# QCW_MMC_PCBA.net
KiCad netlist of a schematic drawn in Altium Designer
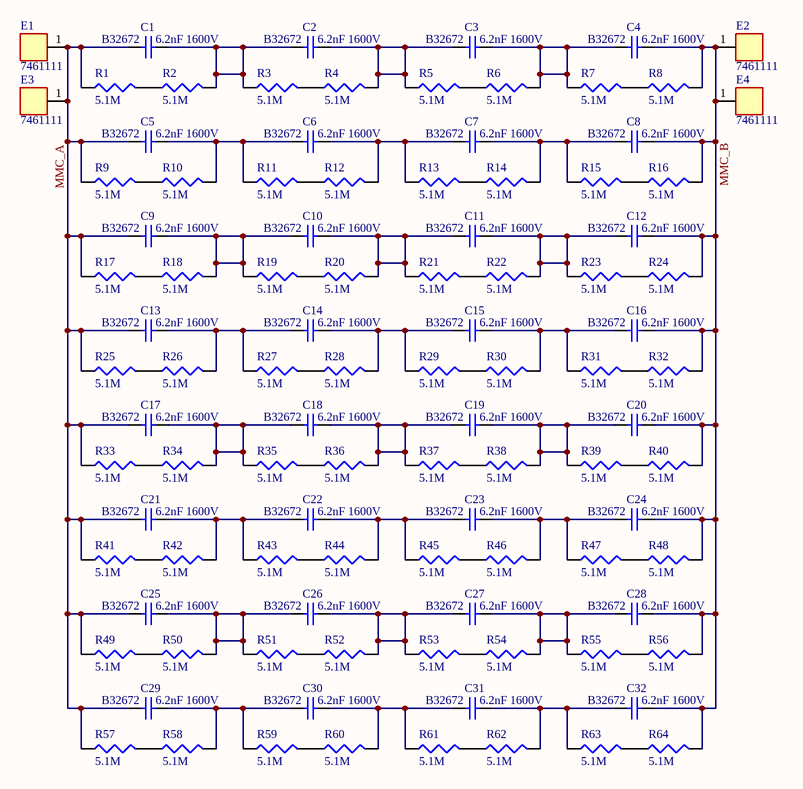
[diagram p0: QCW MMC PCBA.SchDoc]

(export (version "E")
  (design (tool "Eeschema 10.0.6"))
  (components
    (comp (ref "C1")
      (value "B32672")
      (footprint "B32672 6n2 1600V")
      (description "Capacitor")
      (fields (field (name "ALTIUM_VALUE") "6.2nF 1600V") (field (name "PUBLISHER") "Altium Limited"))
      (libsource (lib "Miscellaneous Devices") (part "Cap"))
    )
    (comp (ref "C2")
      (value "B32672")
      (footprint "B32672 6n2 1600V")
      (description "Capacitor")
      (fields (field (name "ALTIUM_VALUE") "6.2nF 1600V") (field (name "PUBLISHER") "Altium Limited"))
      (libsource (lib "Miscellaneous Devices") (part "Cap"))
    )
    (comp (ref "C3")
      (value "B32672")
      (footprint "B32672 6n2 1600V")
      (description "Capacitor")
      (fields (field (name "ALTIUM_VALUE") "6.2nF 1600V") (field (name "PUBLISHER") "Altium Limited"))
      (libsource (lib "Miscellaneous Devices") (part "Cap"))
    )
    (comp (ref "C4")
      (value "B32672")
      (footprint "B32672 6n2 1600V")
      (description "Capacitor")
      (fields (field (name "ALTIUM_VALUE") "6.2nF 1600V") (field (name "PUBLISHER") "Altium Limited"))
      (libsource (lib "Miscellaneous Devices") (part "Cap"))
    )
    (comp (ref "C5")
      (value "B32672")
      (footprint "B32672 6n2 1600V")
      (description "Capacitor")
      (fields (field (name "ALTIUM_VALUE") "6.2nF 1600V") (field (name "PUBLISHER") "Altium Limited"))
      (libsource (lib "Miscellaneous Devices") (part "Cap"))
    )
    (comp (ref "C6")
      (value "B32672")
      (footprint "B32672 6n2 1600V")
      (description "Capacitor")
      (fields (field (name "ALTIUM_VALUE") "6.2nF 1600V") (field (name "PUBLISHER") "Altium Limited"))
      (libsource (lib "Miscellaneous Devices") (part "Cap"))
    )
    (comp (ref "C7")
      (value "B32672")
      (footprint "B32672 6n2 1600V")
      (description "Capacitor")
      (fields (field (name "ALTIUM_VALUE") "6.2nF 1600V") (field (name "PUBLISHER") "Altium Limited"))
      (libsource (lib "Miscellaneous Devices") (part "Cap"))
    )
    (comp (ref "C8")
      (value "B32672")
      (footprint "B32672 6n2 1600V")
      (description "Capacitor")
      (fields (field (name "ALTIUM_VALUE") "6.2nF 1600V") (field (name "PUBLISHER") "Altium Limited"))
      (libsource (lib "Miscellaneous Devices") (part "Cap"))
    )
    (comp (ref "C9")
      (value "B32672")
      (footprint "B32672 6n2 1600V")
      (description "Capacitor")
      (fields (field (name "ALTIUM_VALUE") "6.2nF 1600V") (field (name "PUBLISHER") "Altium Limited"))
      (libsource (lib "Miscellaneous Devices") (part "Cap"))
    )
    (comp (ref "C10")
      (value "B32672")
      (footprint "B32672 6n2 1600V")
      (description "Capacitor")
      (fields (field (name "ALTIUM_VALUE") "6.2nF 1600V") (field (name "PUBLISHER") "Altium Limited"))
      (libsource (lib "Miscellaneous Devices") (part "Cap"))
    )
    (comp (ref "C11")
      (value "B32672")
      (footprint "B32672 6n2 1600V")
      (description "Capacitor")
      (fields (field (name "ALTIUM_VALUE") "6.2nF 1600V") (field (name "PUBLISHER") "Altium Limited"))
      (libsource (lib "Miscellaneous Devices") (part "Cap"))
    )
    (comp (ref "C12")
      (value "B32672")
      (footprint "B32672 6n2 1600V")
      (description "Capacitor")
      (fields (field (name "ALTIUM_VALUE") "6.2nF 1600V") (field (name "PUBLISHER") "Altium Limited"))
      (libsource (lib "Miscellaneous Devices") (part "Cap"))
    )
    (comp (ref "C13")
      (value "B32672")
      (footprint "B32672 6n2 1600V")
      (description "Capacitor")
      (fields (field (name "ALTIUM_VALUE") "6.2nF 1600V") (field (name "PUBLISHER") "Altium Limited"))
      (libsource (lib "Miscellaneous Devices") (part "Cap"))
    )
    (comp (ref "C14")
      (value "B32672")
      (footprint "B32672 6n2 1600V")
      (description "Capacitor")
      (fields (field (name "ALTIUM_VALUE") "6.2nF 1600V") (field (name "PUBLISHER") "Altium Limited"))
      (libsource (lib "Miscellaneous Devices") (part "Cap"))
    )
    (comp (ref "C15")
      (value "B32672")
      (footprint "B32672 6n2 1600V")
      (description "Capacitor")
      (fields (field (name "ALTIUM_VALUE") "6.2nF 1600V") (field (name "PUBLISHER") "Altium Limited"))
      (libsource (lib "Miscellaneous Devices") (part "Cap"))
    )
    (comp (ref "C16")
      (value "B32672")
      (footprint "B32672 6n2 1600V")
      (description "Capacitor")
      (fields (field (name "ALTIUM_VALUE") "6.2nF 1600V") (field (name "PUBLISHER") "Altium Limited"))
      (libsource (lib "Miscellaneous Devices") (part "Cap"))
    )
    (comp (ref "C17")
      (value "B32672")
      (footprint "B32672 6n2 1600V")
      (description "Capacitor")
      (fields (field (name "ALTIUM_VALUE") "6.2nF 1600V") (field (name "PUBLISHER") "Altium Limited"))
      (libsource (lib "Miscellaneous Devices") (part "Cap"))
    )
    (comp (ref "C18")
      (value "B32672")
      (footprint "B32672 6n2 1600V")
      (description "Capacitor")
      (fields (field (name "ALTIUM_VALUE") "6.2nF 1600V") (field (name "PUBLISHER") "Altium Limited"))
      (libsource (lib "Miscellaneous Devices") (part "Cap"))
    )
    (comp (ref "C19")
      (value "B32672")
      (footprint "B32672 6n2 1600V")
      (description "Capacitor")
      (fields (field (name "ALTIUM_VALUE") "6.2nF 1600V") (field (name "PUBLISHER") "Altium Limited"))
      (libsource (lib "Miscellaneous Devices") (part "Cap"))
    )
    (comp (ref "C20")
      (value "B32672")
      (footprint "B32672 6n2 1600V")
      (description "Capacitor")
      (fields (field (name "ALTIUM_VALUE") "6.2nF 1600V") (field (name "PUBLISHER") "Altium Limited"))
      (libsource (lib "Miscellaneous Devices") (part "Cap"))
    )
    (comp (ref "C21")
      (value "B32672")
      (footprint "B32672 6n2 1600V")
      (description "Capacitor")
      (fields (field (name "ALTIUM_VALUE") "6.2nF 1600V") (field (name "PUBLISHER") "Altium Limited"))
      (libsource (lib "Miscellaneous Devices") (part "Cap"))
    )
    (comp (ref "C22")
      (value "B32672")
      (footprint "B32672 6n2 1600V")
      (description "Capacitor")
      (fields (field (name "ALTIUM_VALUE") "6.2nF 1600V") (field (name "PUBLISHER") "Altium Limited"))
      (libsource (lib "Miscellaneous Devices") (part "Cap"))
    )
    (comp (ref "C23")
      (value "B32672")
      (footprint "B32672 6n2 1600V")
      (description "Capacitor")
      (fields (field (name "ALTIUM_VALUE") "6.2nF 1600V") (field (name "PUBLISHER") "Altium Limited"))
      (libsource (lib "Miscellaneous Devices") (part "Cap"))
    )
    (comp (ref "C24")
      (value "B32672")
      (footprint "B32672 6n2 1600V")
      (description "Capacitor")
      (fields (field (name "ALTIUM_VALUE") "6.2nF 1600V") (field (name "PUBLISHER") "Altium Limited"))
      (libsource (lib "Miscellaneous Devices") (part "Cap"))
    )
    (comp (ref "C25")
      (value "B32672")
      (footprint "B32672 6n2 1600V")
      (description "Capacitor")
      (fields (field (name "ALTIUM_VALUE") "6.2nF 1600V") (field (name "PUBLISHER") "Altium Limited"))
      (libsource (lib "Miscellaneous Devices") (part "Cap"))
    )
    (comp (ref "C26")
      (value "B32672")
      (footprint "B32672 6n2 1600V")
      (description "Capacitor")
      (fields (field (name "ALTIUM_VALUE") "6.2nF 1600V") (field (name "PUBLISHER") "Altium Limited"))
      (libsource (lib "Miscellaneous Devices") (part "Cap"))
    )
    (comp (ref "C27")
      (value "B32672")
      (footprint "B32672 6n2 1600V")
      (description "Capacitor")
      (fields (field (name "ALTIUM_VALUE") "6.2nF 1600V") (field (name "PUBLISHER") "Altium Limited"))
      (libsource (lib "Miscellaneous Devices") (part "Cap"))
    )
    (comp (ref "C28")
      (value "B32672")
      (footprint "B32672 6n2 1600V")
      (description "Capacitor")
      (fields (field (name "ALTIUM_VALUE") "6.2nF 1600V") (field (name "PUBLISHER") "Altium Limited"))
      (libsource (lib "Miscellaneous Devices") (part "Cap"))
    )
    (comp (ref "C29")
      (value "B32672")
      (footprint "B32672 6n2 1600V")
      (description "Capacitor")
      (fields (field (name "ALTIUM_VALUE") "6.2nF 1600V") (field (name "PUBLISHER") "Altium Limited"))
      (libsource (lib "Miscellaneous Devices") (part "Cap"))
    )
    (comp (ref "C30")
      (value "B32672")
      (footprint "B32672 6n2 1600V")
      (description "Capacitor")
      (fields (field (name "ALTIUM_VALUE") "6.2nF 1600V") (field (name "PUBLISHER") "Altium Limited"))
      (libsource (lib "Miscellaneous Devices") (part "Cap"))
    )
    (comp (ref "C31")
      (value "B32672")
      (footprint "B32672 6n2 1600V")
      (description "Capacitor")
      (fields (field (name "ALTIUM_VALUE") "6.2nF 1600V") (field (name "PUBLISHER") "Altium Limited"))
      (libsource (lib "Miscellaneous Devices") (part "Cap"))
    )
    (comp (ref "C32")
      (value "B32672")
      (footprint "B32672 6n2 1600V")
      (description "Capacitor")
      (fields (field (name "ALTIUM_VALUE") "6.2nF 1600V") (field (name "PUBLISHER") "Altium Limited"))
      (libsource (lib "Miscellaneous Devices") (part "Cap"))
    )
    (comp (ref "E1")
      (value "7461111")
      (footprint "7461111_HAL Surface")
      (description "WP-RAFU 90° with Full Plain Pin Plate, M4, thr 5mm")
      (fields (field (name "MANUFACTURER") "Wurth Elektronik") (field (name "CREATED BY") "Baojun Chen"))
      (libsource (lib "TV_Altium_library") (part "WP-RAFU,  7461111"))
    )
    (comp (ref "E2")
      (value "7461111")
      (footprint "7461111_HAL Surface")
      (description "WP-RAFU 90° with Full Plain Pin Plate, M4, thr 5mm")
      (fields (field (name "MANUFACTURER") "Wurth Elektronik") (field (name "CREATED BY") "Baojun Chen"))
      (libsource (lib "") (part "WP-RAFU,  7461111_1"))
    )
    (comp (ref "E3")
      (value "7461111")
      (footprint "7461111_HAL Surface")
      (description "WP-RAFU 90° with Full Plain Pin Plate, M4, thr 5mm")
      (fields (field (name "MANUFACTURER") "Wurth Elektronik") (field (name "CREATED BY") "Baojun Chen"))
      (libsource (lib "TV_Altium_library") (part "WP-RAFU,  7461111"))
    )
    (comp (ref "E4")
      (value "7461111")
      (footprint "7461111_HAL Surface")
      (description "WP-RAFU 90° with Full Plain Pin Plate, M4, thr 5mm")
      (fields (field (name "MANUFACTURER") "Wurth Elektronik") (field (name "CREATED BY") "Baojun Chen"))
      (libsource (lib "") (part "WP-RAFU,  7461111_1"))
    )
    (comp (ref "R1")
      (value "5.1M")
      (description "Resistor")
      (fields (field (name "Comment") "HV 1206 Resistor") (field (name "PUBLISHER") "Altium Limited"))
      (libsource (lib "Miscellaneous Devices") (part "Res3"))
    )
    (comp (ref "R2")
      (value "5.1M")
      (description "Resistor")
      (fields (field (name "Comment") "HV 1206 Resistor") (field (name "PUBLISHER") "Altium Limited"))
      (libsource (lib "Miscellaneous Devices") (part "Res3"))
    )
    (comp (ref "R3")
      (value "5.1M")
      (description "Resistor")
      (fields (field (name "Comment") "HV 1206 Resistor") (field (name "PUBLISHER") "Altium Limited"))
      (libsource (lib "Miscellaneous Devices") (part "Res3"))
    )
    (comp (ref "R4")
      (value "5.1M")
      (description "Resistor")
      (fields (field (name "Comment") "HV 1206 Resistor") (field (name "PUBLISHER") "Altium Limited"))
      (libsource (lib "Miscellaneous Devices") (part "Res3"))
    )
    (comp (ref "R5")
      (value "5.1M")
      (description "Resistor")
      (fields (field (name "Comment") "HV 1206 Resistor") (field (name "PUBLISHER") "Altium Limited"))
      (libsource (lib "Miscellaneous Devices") (part "Res3"))
    )
    (comp (ref "R6")
      (value "5.1M")
      (description "Resistor")
      (fields (field (name "Comment") "HV 1206 Resistor") (field (name "PUBLISHER") "Altium Limited"))
      (libsource (lib "Miscellaneous Devices") (part "Res3"))
    )
    (comp (ref "R7")
      (value "5.1M")
      (description "Resistor")
      (fields (field (name "Comment") "HV 1206 Resistor") (field (name "PUBLISHER") "Altium Limited"))
      (libsource (lib "Miscellaneous Devices") (part "Res3"))
    )
    (comp (ref "R8")
      (value "5.1M")
      (description "Resistor")
      (fields (field (name "Comment") "HV 1206 Resistor") (field (name "PUBLISHER") "Altium Limited"))
      (libsource (lib "Miscellaneous Devices") (part "Res3"))
    )
    (comp (ref "R9")
      (value "5.1M")
      (description "Resistor")
      (fields (field (name "Comment") "HV 1206 Resistor") (field (name "PUBLISHER") "Altium Limited"))
      (libsource (lib "Miscellaneous Devices") (part "Res3"))
    )
    (comp (ref "R10")
      (value "5.1M")
      (description "Resistor")
      (fields (field (name "Comment") "HV 1206 Resistor") (field (name "PUBLISHER") "Altium Limited"))
      (libsource (lib "Miscellaneous Devices") (part "Res3"))
    )
    (comp (ref "R11")
      (value "5.1M")
      (description "Resistor")
      (fields (field (name "Comment") "HV 1206 Resistor") (field (name "PUBLISHER") "Altium Limited"))
      (libsource (lib "Miscellaneous Devices") (part "Res3"))
    )
    (comp (ref "R12")
      (value "5.1M")
      (description "Resistor")
      (fields (field (name "Comment") "HV 1206 Resistor") (field (name "PUBLISHER") "Altium Limited"))
      (libsource (lib "Miscellaneous Devices") (part "Res3"))
    )
    (comp (ref "R13")
      (value "5.1M")
      (description "Resistor")
      (fields (field (name "Comment") "HV 1206 Resistor") (field (name "PUBLISHER") "Altium Limited"))
      (libsource (lib "Miscellaneous Devices") (part "Res3"))
    )
    (comp (ref "R14")
      (value "5.1M")
      (description "Resistor")
      (fields (field (name "Comment") "HV 1206 Resistor") (field (name "PUBLISHER") "Altium Limited"))
      (libsource (lib "Miscellaneous Devices") (part "Res3"))
    )
    (comp (ref "R15")
      (value "5.1M")
      (description "Resistor")
      (fields (field (name "Comment") "HV 1206 Resistor") (field (name "PUBLISHER") "Altium Limited"))
      (libsource (lib "Miscellaneous Devices") (part "Res3"))
    )
    (comp (ref "R16")
      (value "5.1M")
      (description "Resistor")
      (fields (field (name "Comment") "HV 1206 Resistor") (field (name "PUBLISHER") "Altium Limited"))
      (libsource (lib "Miscellaneous Devices") (part "Res3"))
    )
    (comp (ref "R17")
      (value "5.1M")
      (description "Resistor")
      (fields (field (name "Comment") "HV 1206 Resistor") (field (name "PUBLISHER") "Altium Limited"))
      (libsource (lib "Miscellaneous Devices") (part "Res3"))
    )
    (comp (ref "R18")
      (value "5.1M")
      (description "Resistor")
      (fields (field (name "Comment") "HV 1206 Resistor") (field (name "PUBLISHER") "Altium Limited"))
      (libsource (lib "Miscellaneous Devices") (part "Res3"))
    )
    (comp (ref "R19")
      (value "5.1M")
      (description "Resistor")
      (fields (field (name "Comment") "HV 1206 Resistor") (field (name "PUBLISHER") "Altium Limited"))
      (libsource (lib "Miscellaneous Devices") (part "Res3"))
    )
    (comp (ref "R20")
      (value "5.1M")
      (description "Resistor")
      (fields (field (name "Comment") "HV 1206 Resistor") (field (name "PUBLISHER") "Altium Limited"))
      (libsource (lib "Miscellaneous Devices") (part "Res3"))
    )
    (comp (ref "R21")
      (value "5.1M")
      (description "Resistor")
      (fields (field (name "Comment") "HV 1206 Resistor") (field (name "PUBLISHER") "Altium Limited"))
      (libsource (lib "Miscellaneous Devices") (part "Res3"))
    )
    (comp (ref "R22")
      (value "5.1M")
      (description "Resistor")
      (fields (field (name "Comment") "HV 1206 Resistor") (field (name "PUBLISHER") "Altium Limited"))
      (libsource (lib "Miscellaneous Devices") (part "Res3"))
    )
    (comp (ref "R23")
      (value "5.1M")
      (description "Resistor")
      (fields (field (name "Comment") "HV 1206 Resistor") (field (name "PUBLISHER") "Altium Limited"))
      (libsource (lib "Miscellaneous Devices") (part "Res3"))
    )
    (comp (ref "R24")
      (value "5.1M")
      (description "Resistor")
      (fields (field (name "Comment") "HV 1206 Resistor") (field (name "PUBLISHER") "Altium Limited"))
      (libsource (lib "Miscellaneous Devices") (part "Res3"))
    )
    (comp (ref "R25")
      (value "5.1M")
      (description "Resistor")
      (fields (field (name "Comment") "HV 1206 Resistor") (field (name "PUBLISHER") "Altium Limited"))
      (libsource (lib "Miscellaneous Devices") (part "Res3"))
    )
    (comp (ref "R26")
      (value "5.1M")
      (description "Resistor")
      (fields (field (name "Comment") "HV 1206 Resistor") (field (name "PUBLISHER") "Altium Limited"))
      (libsource (lib "Miscellaneous Devices") (part "Res3"))
    )
    (comp (ref "R27")
      (value "5.1M")
      (description "Resistor")
      (fields (field (name "Comment") "HV 1206 Resistor") (field (name "PUBLISHER") "Altium Limited"))
      (libsource (lib "Miscellaneous Devices") (part "Res3"))
    )
    (comp (ref "R28")
      (value "5.1M")
      (description "Resistor")
      (fields (field (name "Comment") "HV 1206 Resistor") (field (name "PUBLISHER") "Altium Limited"))
      (libsource (lib "Miscellaneous Devices") (part "Res3"))
    )
    (comp (ref "R29")
      (value "5.1M")
      (description "Resistor")
      (fields (field (name "Comment") "HV 1206 Resistor") (field (name "PUBLISHER") "Altium Limited"))
      (libsource (lib "Miscellaneous Devices") (part "Res3"))
    )
    (comp (ref "R30")
      (value "5.1M")
      (description "Resistor")
      (fields (field (name "Comment") "HV 1206 Resistor") (field (name "PUBLISHER") "Altium Limited"))
      (libsource (lib "Miscellaneous Devices") (part "Res3"))
    )
    (comp (ref "R31")
      (value "5.1M")
      (description "Resistor")
      (fields (field (name "Comment") "HV 1206 Resistor") (field (name "PUBLISHER") "Altium Limited"))
      (libsource (lib "Miscellaneous Devices") (part "Res3"))
    )
    (comp (ref "R32")
      (value "5.1M")
      (description "Resistor")
      (fields (field (name "Comment") "HV 1206 Resistor") (field (name "PUBLISHER") "Altium Limited"))
      (libsource (lib "Miscellaneous Devices") (part "Res3"))
    )
    (comp (ref "R33")
      (value "5.1M")
      (description "Resistor")
      (fields (field (name "Comment") "HV 1206 Resistor") (field (name "PUBLISHER") "Altium Limited"))
      (libsource (lib "Miscellaneous Devices") (part "Res3"))
    )
    (comp (ref "R34")
      (value "5.1M")
      (description "Resistor")
      (fields (field (name "Comment") "HV 1206 Resistor") (field (name "PUBLISHER") "Altium Limited"))
      (libsource (lib "Miscellaneous Devices") (part "Res3"))
    )
    (comp (ref "R35")
      (value "5.1M")
      (description "Resistor")
      (fields (field (name "Comment") "HV 1206 Resistor") (field (name "PUBLISHER") "Altium Limited"))
      (libsource (lib "Miscellaneous Devices") (part "Res3"))
    )
    (comp (ref "R36")
      (value "5.1M")
      (description "Resistor")
      (fields (field (name "Comment") "HV 1206 Resistor") (field (name "PUBLISHER") "Altium Limited"))
      (libsource (lib "Miscellaneous Devices") (part "Res3"))
    )
    (comp (ref "R37")
      (value "5.1M")
      (description "Resistor")
      (fields (field (name "Comment") "HV 1206 Resistor") (field (name "PUBLISHER") "Altium Limited"))
      (libsource (lib "Miscellaneous Devices") (part "Res3"))
    )
    (comp (ref "R38")
      (value "5.1M")
      (description "Resistor")
      (fields (field (name "Comment") "HV 1206 Resistor") (field (name "PUBLISHER") "Altium Limited"))
      (libsource (lib "Miscellaneous Devices") (part "Res3"))
    )
    (comp (ref "R39")
      (value "5.1M")
      (description "Resistor")
      (fields (field (name "Comment") "HV 1206 Resistor") (field (name "PUBLISHER") "Altium Limited"))
      (libsource (lib "Miscellaneous Devices") (part "Res3"))
    )
    (comp (ref "R40")
      (value "5.1M")
      (description "Resistor")
      (fields (field (name "Comment") "HV 1206 Resistor") (field (name "PUBLISHER") "Altium Limited"))
      (libsource (lib "Miscellaneous Devices") (part "Res3"))
    )
    (comp (ref "R41")
      (value "5.1M")
      (description "Resistor")
      (fields (field (name "Comment") "HV 1206 Resistor") (field (name "PUBLISHER") "Altium Limited"))
      (libsource (lib "Miscellaneous Devices") (part "Res3"))
    )
    (comp (ref "R42")
      (value "5.1M")
      (description "Resistor")
      (fields (field (name "Comment") "HV 1206 Resistor") (field (name "PUBLISHER") "Altium Limited"))
      (libsource (lib "Miscellaneous Devices") (part "Res3"))
    )
    (comp (ref "R43")
      (value "5.1M")
      (description "Resistor")
      (fields (field (name "Comment") "HV 1206 Resistor") (field (name "PUBLISHER") "Altium Limited"))
      (libsource (lib "Miscellaneous Devices") (part "Res3"))
    )
    (comp (ref "R44")
      (value "5.1M")
      (description "Resistor")
      (fields (field (name "Comment") "HV 1206 Resistor") (field (name "PUBLISHER") "Altium Limited"))
      (libsource (lib "Miscellaneous Devices") (part "Res3"))
    )
    (comp (ref "R45")
      (value "5.1M")
      (description "Resistor")
      (fields (field (name "Comment") "HV 1206 Resistor") (field (name "PUBLISHER") "Altium Limited"))
      (libsource (lib "Miscellaneous Devices") (part "Res3"))
    )
    (comp (ref "R46")
      (value "5.1M")
      (description "Resistor")
      (fields (field (name "Comment") "HV 1206 Resistor") (field (name "PUBLISHER") "Altium Limited"))
      (libsource (lib "Miscellaneous Devices") (part "Res3"))
    )
    (comp (ref "R47")
      (value "5.1M")
      (description "Resistor")
      (fields (field (name "Comment") "HV 1206 Resistor") (field (name "PUBLISHER") "Altium Limited"))
      (libsource (lib "Miscellaneous Devices") (part "Res3"))
    )
    (comp (ref "R48")
      (value "5.1M")
      (description "Resistor")
      (fields (field (name "Comment") "HV 1206 Resistor") (field (name "PUBLISHER") "Altium Limited"))
      (libsource (lib "Miscellaneous Devices") (part "Res3"))
    )
    (comp (ref "R49")
      (value "5.1M")
      (description "Resistor")
      (fields (field (name "Comment") "HV 1206 Resistor") (field (name "PUBLISHER") "Altium Limited"))
      (libsource (lib "Miscellaneous Devices") (part "Res3"))
    )
    (comp (ref "R50")
      (value "5.1M")
      (description "Resistor")
      (fields (field (name "Comment") "HV 1206 Resistor") (field (name "PUBLISHER") "Altium Limited"))
      (libsource (lib "Miscellaneous Devices") (part "Res3"))
    )
    (comp (ref "R51")
      (value "5.1M")
      (description "Resistor")
      (fields (field (name "Comment") "HV 1206 Resistor") (field (name "PUBLISHER") "Altium Limited"))
      (libsource (lib "Miscellaneous Devices") (part "Res3"))
    )
    (comp (ref "R52")
      (value "5.1M")
      (description "Resistor")
      (fields (field (name "Comment") "HV 1206 Resistor") (field (name "PUBLISHER") "Altium Limited"))
      (libsource (lib "Miscellaneous Devices") (part "Res3"))
    )
    (comp (ref "R53")
      (value "5.1M")
      (description "Resistor")
      (fields (field (name "Comment") "HV 1206 Resistor") (field (name "PUBLISHER") "Altium Limited"))
      (libsource (lib "Miscellaneous Devices") (part "Res3"))
    )
    (comp (ref "R54")
      (value "5.1M")
      (description "Resistor")
      (fields (field (name "Comment") "HV 1206 Resistor") (field (name "PUBLISHER") "Altium Limited"))
      (libsource (lib "Miscellaneous Devices") (part "Res3"))
    )
    (comp (ref "R55")
      (value "5.1M")
      (description "Resistor")
      (fields (field (name "Comment") "HV 1206 Resistor") (field (name "PUBLISHER") "Altium Limited"))
      (libsource (lib "Miscellaneous Devices") (part "Res3"))
    )
    (comp (ref "R56")
      (value "5.1M")
      (description "Resistor")
      (fields (field (name "Comment") "HV 1206 Resistor") (field (name "PUBLISHER") "Altium Limited"))
      (libsource (lib "Miscellaneous Devices") (part "Res3"))
    )
    (comp (ref "R57")
      (value "5.1M")
      (description "Resistor")
      (fields (field (name "Comment") "HV 1206 Resistor") (field (name "PUBLISHER") "Altium Limited"))
      (libsource (lib "Miscellaneous Devices") (part "Res3"))
    )
    (comp (ref "R58")
      (value "5.1M")
      (description "Resistor")
      (fields (field (name "Comment") "HV 1206 Resistor") (field (name "PUBLISHER") "Altium Limited"))
      (libsource (lib "Miscellaneous Devices") (part "Res3"))
    )
    (comp (ref "R59")
      (value "5.1M")
      (description "Resistor")
      (fields (field (name "Comment") "HV 1206 Resistor") (field (name "PUBLISHER") "Altium Limited"))
      (libsource (lib "Miscellaneous Devices") (part "Res3"))
    )
    (comp (ref "R60")
      (value "5.1M")
      (description "Resistor")
      (fields (field (name "Comment") "HV 1206 Resistor") (field (name "PUBLISHER") "Altium Limited"))
      (libsource (lib "Miscellaneous Devices") (part "Res3"))
    )
    (comp (ref "R61")
      (value "5.1M")
      (description "Resistor")
      (fields (field (name "Comment") "HV 1206 Resistor") (field (name "PUBLISHER") "Altium Limited"))
      (libsource (lib "Miscellaneous Devices") (part "Res3"))
    )
    (comp (ref "R62")
      (value "5.1M")
      (description "Resistor")
      (fields (field (name "Comment") "HV 1206 Resistor") (field (name "PUBLISHER") "Altium Limited"))
      (libsource (lib "Miscellaneous Devices") (part "Res3"))
    )
    (comp (ref "R63")
      (value "5.1M")
      (description "Resistor")
      (fields (field (name "Comment") "HV 1206 Resistor") (field (name "PUBLISHER") "Altium Limited"))
      (libsource (lib "Miscellaneous Devices") (part "Res3"))
    )
    (comp (ref "R64")
      (value "5.1M")
      (description "Resistor")
      (fields (field (name "Comment") "HV 1206 Resistor") (field (name "PUBLISHER") "Altium Limited"))
      (libsource (lib "Miscellaneous Devices") (part "Res3"))
    )
  )
  (nets
    (net (code "1") (name "/MMC_A") (class "Default")
      (node (ref "C1") (pin "1") (pinfunction "1_1") (pintype "passive"))
      (node (ref "C13") (pin "1") (pinfunction "1_1") (pintype "passive"))
      (node (ref "C17") (pin "1") (pinfunction "1_1") (pintype "passive"))
      (node (ref "C21") (pin "1") (pinfunction "1_1") (pintype "passive"))
      (node (ref "C25") (pin "1") (pinfunction "1_1") (pintype "passive"))
      (node (ref "C29") (pin "1") (pinfunction "1_1") (pintype "passive"))
      (node (ref "C5") (pin "1") (pinfunction "1_1") (pintype "passive"))
      (node (ref "C9") (pin "1") (pinfunction "1_1") (pintype "passive"))
      (node (ref "E1") (pin "1") (pinfunction "1_1") (pintype "passive"))
      (node (ref "E3") (pin "1") (pinfunction "1_1") (pintype "passive"))
      (node (ref "R1") (pin "1") (pinfunction "1_1") (pintype "passive"))
      (node (ref "R17") (pin "1") (pinfunction "1_1") (pintype "passive"))
      (node (ref "R25") (pin "1") (pinfunction "1_1") (pintype "passive"))
      (node (ref "R33") (pin "1") (pinfunction "1_1") (pintype "passive"))
      (node (ref "R41") (pin "1") (pinfunction "1_1") (pintype "passive"))
      (node (ref "R49") (pin "1") (pinfunction "1_1") (pintype "passive"))
      (node (ref "R57") (pin "1") (pinfunction "1_1") (pintype "passive"))
      (node (ref "R9") (pin "1") (pinfunction "1_1") (pintype "passive"))
    )
    (net (code "2") (name "/MMC_B") (class "Default")
      (node (ref "C12") (pin "2") (pinfunction "2_2") (pintype "passive"))
      (node (ref "C16") (pin "2") (pinfunction "2_2") (pintype "passive"))
      (node (ref "C20") (pin "2") (pinfunction "2_2") (pintype "passive"))
      (node (ref "C24") (pin "2") (pinfunction "2_2") (pintype "passive"))
      (node (ref "C28") (pin "2") (pinfunction "2_2") (pintype "passive"))
      (node (ref "C32") (pin "2") (pinfunction "2_2") (pintype "passive"))
      (node (ref "C4") (pin "2") (pinfunction "2_2") (pintype "passive"))
      (node (ref "C8") (pin "2") (pinfunction "2_2") (pintype "passive"))
      (node (ref "E2") (pin "1") (pinfunction "1_1") (pintype "passive"))
      (node (ref "E4") (pin "1") (pinfunction "1_1") (pintype "passive"))
      (node (ref "R16") (pin "2") (pinfunction "2_2") (pintype "passive"))
      (node (ref "R24") (pin "2") (pinfunction "2_2") (pintype "passive"))
      (node (ref "R32") (pin "2") (pinfunction "2_2") (pintype "passive"))
      (node (ref "R40") (pin "2") (pinfunction "2_2") (pintype "passive"))
      (node (ref "R48") (pin "2") (pinfunction "2_2") (pintype "passive"))
      (node (ref "R56") (pin "2") (pinfunction "2_2") (pintype "passive"))
      (node (ref "R64") (pin "2") (pinfunction "2_2") (pintype "passive"))
      (node (ref "R8") (pin "2") (pinfunction "2_2") (pintype "passive"))
    )
    (net (code "3") (name "Net-(C1-Pad2)") (class "Default")
      (node (ref "C1") (pin "2") (pinfunction "2_2") (pintype "passive"))
      (node (ref "C2") (pin "1") (pinfunction "1_1") (pintype "passive"))
      (node (ref "R2") (pin "2") (pinfunction "2_2") (pintype "passive"))
      (node (ref "R3") (pin "1") (pinfunction "1_1") (pintype "passive"))
    )
    (net (code "4") (name "Net-(C2-Pad2)") (class "Default")
      (node (ref "C2") (pin "2") (pinfunction "2_2") (pintype "passive"))
      (node (ref "C3") (pin "1") (pinfunction "1_1") (pintype "passive"))
      (node (ref "R4") (pin "2") (pinfunction "2_2") (pintype "passive"))
      (node (ref "R5") (pin "1") (pinfunction "1_1") (pintype "passive"))
    )
    (net (code "5") (name "Net-(C3-Pad2)") (class "Default")
      (node (ref "C3") (pin "2") (pinfunction "2_2") (pintype "passive"))
      (node (ref "C4") (pin "1") (pinfunction "1_1") (pintype "passive"))
      (node (ref "R6") (pin "2") (pinfunction "2_2") (pintype "passive"))
      (node (ref "R7") (pin "1") (pinfunction "1_1") (pintype "passive"))
    )
    (net (code "6") (name "Net-(C5-Pad2)") (class "Default")
      (node (ref "C5") (pin "2") (pinfunction "2_2") (pintype "passive"))
      (node (ref "C6") (pin "1") (pinfunction "1_1") (pintype "passive"))
      (node (ref "R10") (pin "2") (pinfunction "2_2") (pintype "passive"))
      (node (ref "R11") (pin "1") (pinfunction "1_1") (pintype "passive"))
    )
    (net (code "7") (name "Net-(C6-Pad2)") (class "Default")
      (node (ref "C6") (pin "2") (pinfunction "2_2") (pintype "passive"))
      (node (ref "C7") (pin "1") (pinfunction "1_1") (pintype "passive"))
      (node (ref "R12") (pin "2") (pinfunction "2_2") (pintype "passive"))
      (node (ref "R13") (pin "1") (pinfunction "1_1") (pintype "passive"))
    )
    (net (code "8") (name "Net-(C7-Pad2)") (class "Default")
      (node (ref "C7") (pin "2") (pinfunction "2_2") (pintype "passive"))
      (node (ref "C8") (pin "1") (pinfunction "1_1") (pintype "passive"))
      (node (ref "R14") (pin "2") (pinfunction "2_2") (pintype "passive"))
      (node (ref "R15") (pin "1") (pinfunction "1_1") (pintype "passive"))
    )
    (net (code "9") (name "Net-(C10-Pad1)") (class "Default")
      (node (ref "C10") (pin "1") (pinfunction "1_1") (pintype "passive"))
      (node (ref "C9") (pin "2") (pinfunction "2_2") (pintype "passive"))
      (node (ref "R18") (pin "2") (pinfunction "2_2") (pintype "passive"))
      (node (ref "R19") (pin "1") (pinfunction "1_1") (pintype "passive"))
    )
    (net (code "10") (name "Net-(C10-Pad2)") (class "Default")
      (node (ref "C10") (pin "2") (pinfunction "2_2") (pintype "passive"))
      (node (ref "C11") (pin "1") (pinfunction "1_1") (pintype "passive"))
      (node (ref "R20") (pin "2") (pinfunction "2_2") (pintype "passive"))
      (node (ref "R21") (pin "1") (pinfunction "1_1") (pintype "passive"))
    )
    (net (code "11") (name "Net-(C11-Pad2)") (class "Default")
      (node (ref "C11") (pin "2") (pinfunction "2_2") (pintype "passive"))
      (node (ref "C12") (pin "1") (pinfunction "1_1") (pintype "passive"))
      (node (ref "R22") (pin "2") (pinfunction "2_2") (pintype "passive"))
      (node (ref "R23") (pin "1") (pinfunction "1_1") (pintype "passive"))
    )
    (net (code "12") (name "Net-(C13-Pad2)") (class "Default")
      (node (ref "C13") (pin "2") (pinfunction "2_2") (pintype "passive"))
      (node (ref "C14") (pin "1") (pinfunction "1_1") (pintype "passive"))
      (node (ref "R26") (pin "2") (pinfunction "2_2") (pintype "passive"))
      (node (ref "R27") (pin "1") (pinfunction "1_1") (pintype "passive"))
    )
    (net (code "13") (name "Net-(C14-Pad2)") (class "Default")
      (node (ref "C14") (pin "2") (pinfunction "2_2") (pintype "passive"))
      (node (ref "C15") (pin "1") (pinfunction "1_1") (pintype "passive"))
      (node (ref "R28") (pin "2") (pinfunction "2_2") (pintype "passive"))
      (node (ref "R29") (pin "1") (pinfunction "1_1") (pintype "passive"))
    )
    (net (code "14") (name "Net-(C15-Pad2)") (class "Default")
      (node (ref "C15") (pin "2") (pinfunction "2_2") (pintype "passive"))
      (node (ref "C16") (pin "1") (pinfunction "1_1") (pintype "passive"))
      (node (ref "R30") (pin "2") (pinfunction "2_2") (pintype "passive"))
      (node (ref "R31") (pin "1") (pinfunction "1_1") (pintype "passive"))
    )
    (net (code "15") (name "Net-(C17-Pad2)") (class "Default")
      (node (ref "C17") (pin "2") (pinfunction "2_2") (pintype "passive"))
      (node (ref "C18") (pin "1") (pinfunction "1_1") (pintype "passive"))
      (node (ref "R34") (pin "2") (pinfunction "2_2") (pintype "passive"))
      (node (ref "R35") (pin "1") (pinfunction "1_1") (pintype "passive"))
    )
    (net (code "16") (name "Net-(C18-Pad2)") (class "Default")
      (node (ref "C18") (pin "2") (pinfunction "2_2") (pintype "passive"))
      (node (ref "C19") (pin "1") (pinfunction "1_1") (pintype "passive"))
      (node (ref "R36") (pin "2") (pinfunction "2_2") (pintype "passive"))
      (node (ref "R37") (pin "1") (pinfunction "1_1") (pintype "passive"))
    )
    (net (code "17") (name "Net-(C19-Pad2)") (class "Default")
      (node (ref "C19") (pin "2") (pinfunction "2_2") (pintype "passive"))
      (node (ref "C20") (pin "1") (pinfunction "1_1") (pintype "passive"))
      (node (ref "R38") (pin "2") (pinfunction "2_2") (pintype "passive"))
      (node (ref "R39") (pin "1") (pinfunction "1_1") (pintype "passive"))
    )
    (net (code "18") (name "Net-(C21-Pad2)") (class "Default")
      (node (ref "C21") (pin "2") (pinfunction "2_2") (pintype "passive"))
      (node (ref "C22") (pin "1") (pinfunction "1_1") (pintype "passive"))
      (node (ref "R42") (pin "2") (pinfunction "2_2") (pintype "passive"))
      (node (ref "R43") (pin "1") (pinfunction "1_1") (pintype "passive"))
    )
    (net (code "19") (name "Net-(C22-Pad2)") (class "Default")
      (node (ref "C22") (pin "2") (pinfunction "2_2") (pintype "passive"))
      (node (ref "C23") (pin "1") (pinfunction "1_1") (pintype "passive"))
      (node (ref "R44") (pin "2") (pinfunction "2_2") (pintype "passive"))
      (node (ref "R45") (pin "1") (pinfunction "1_1") (pintype "passive"))
    )
    (net (code "20") (name "Net-(C23-Pad2)") (class "Default")
      (node (ref "C23") (pin "2") (pinfunction "2_2") (pintype "passive"))
      (node (ref "C24") (pin "1") (pinfunction "1_1") (pintype "passive"))
      (node (ref "R46") (pin "2") (pinfunction "2_2") (pintype "passive"))
      (node (ref "R47") (pin "1") (pinfunction "1_1") (pintype "passive"))
    )
    (net (code "21") (name "Net-(C25-Pad2)") (class "Default")
      (node (ref "C25") (pin "2") (pinfunction "2_2") (pintype "passive"))
      (node (ref "C26") (pin "1") (pinfunction "1_1") (pintype "passive"))
      (node (ref "R50") (pin "2") (pinfunction "2_2") (pintype "passive"))
      (node (ref "R51") (pin "1") (pinfunction "1_1") (pintype "passive"))
    )
    (net (code "22") (name "Net-(C26-Pad2)") (class "Default")
      (node (ref "C26") (pin "2") (pinfunction "2_2") (pintype "passive"))
      (node (ref "C27") (pin "1") (pinfunction "1_1") (pintype "passive"))
      (node (ref "R52") (pin "2") (pinfunction "2_2") (pintype "passive"))
      (node (ref "R53") (pin "1") (pinfunction "1_1") (pintype "passive"))
    )
    (net (code "23") (name "Net-(C27-Pad2)") (class "Default")
      (node (ref "C27") (pin "2") (pinfunction "2_2") (pintype "passive"))
      (node (ref "C28") (pin "1") (pinfunction "1_1") (pintype "passive"))
      (node (ref "R54") (pin "2") (pinfunction "2_2") (pintype "passive"))
      (node (ref "R55") (pin "1") (pinfunction "1_1") (pintype "passive"))
    )
    (net (code "24") (name "Net-(C29-Pad2)") (class "Default")
      (node (ref "C29") (pin "2") (pinfunction "2_2") (pintype "passive"))
      (node (ref "C30") (pin "1") (pinfunction "1_1") (pintype "passive"))
      (node (ref "R58") (pin "2") (pinfunction "2_2") (pintype "passive"))
      (node (ref "R59") (pin "1") (pinfunction "1_1") (pintype "passive"))
    )
    (net (code "25") (name "Net-(C30-Pad2)") (class "Default")
      (node (ref "C30") (pin "2") (pinfunction "2_2") (pintype "passive"))
      (node (ref "C31") (pin "1") (pinfunction "1_1") (pintype "passive"))
      (node (ref "R60") (pin "2") (pinfunction "2_2") (pintype "passive"))
      (node (ref "R61") (pin "1") (pinfunction "1_1") (pintype "passive"))
    )
    (net (code "26") (name "Net-(C31-Pad2)") (class "Default")
      (node (ref "C31") (pin "2") (pinfunction "2_2") (pintype "passive"))
      (node (ref "C32") (pin "1") (pinfunction "1_1") (pintype "passive"))
      (node (ref "R62") (pin "2") (pinfunction "2_2") (pintype "passive"))
      (node (ref "R63") (pin "1") (pinfunction "1_1") (pintype "passive"))
    )
    (net (code "27") (name "Net-(R1-Pad2)") (class "Default")
      (node (ref "R1") (pin "2") (pinfunction "2_2") (pintype "passive"))
      (node (ref "R2") (pin "1") (pinfunction "1_1") (pintype "passive"))
    )
    (net (code "28") (name "Net-(R3-Pad2)") (class "Default")
      (node (ref "R3") (pin "2") (pinfunction "2_2") (pintype "passive"))
      (node (ref "R4") (pin "1") (pinfunction "1_1") (pintype "passive"))
    )
    (net (code "29") (name "Net-(R5-Pad2)") (class "Default")
      (node (ref "R5") (pin "2") (pinfunction "2_2") (pintype "passive"))
      (node (ref "R6") (pin "1") (pinfunction "1_1") (pintype "passive"))
    )
    (net (code "30") (name "Net-(R7-Pad2)") (class "Default")
      (node (ref "R7") (pin "2") (pinfunction "2_2") (pintype "passive"))
      (node (ref "R8") (pin "1") (pinfunction "1_1") (pintype "passive"))
    )
    (net (code "31") (name "Net-(R10-Pad1)") (class "Default")
      (node (ref "R10") (pin "1") (pinfunction "1_1") (pintype "passive"))
      (node (ref "R9") (pin "2") (pinfunction "2_2") (pintype "passive"))
    )
    (net (code "32") (name "Net-(R11-Pad2)") (class "Default")
      (node (ref "R11") (pin "2") (pinfunction "2_2") (pintype "passive"))
      (node (ref "R12") (pin "1") (pinfunction "1_1") (pintype "passive"))
    )
    (net (code "33") (name "Net-(R13-Pad2)") (class "Default")
      (node (ref "R13") (pin "2") (pinfunction "2_2") (pintype "passive"))
      (node (ref "R14") (pin "1") (pinfunction "1_1") (pintype "passive"))
    )
    (net (code "34") (name "Net-(R15-Pad2)") (class "Default")
      (node (ref "R15") (pin "2") (pinfunction "2_2") (pintype "passive"))
      (node (ref "R16") (pin "1") (pinfunction "1_1") (pintype "passive"))
    )
    (net (code "35") (name "Net-(R17-Pad2)") (class "Default")
      (node (ref "R17") (pin "2") (pinfunction "2_2") (pintype "passive"))
      (node (ref "R18") (pin "1") (pinfunction "1_1") (pintype "passive"))
    )
    (net (code "36") (name "Net-(R19-Pad2)") (class "Default")
      (node (ref "R19") (pin "2") (pinfunction "2_2") (pintype "passive"))
      (node (ref "R20") (pin "1") (pinfunction "1_1") (pintype "passive"))
    )
    (net (code "37") (name "Net-(R21-Pad2)") (class "Default")
      (node (ref "R21") (pin "2") (pinfunction "2_2") (pintype "passive"))
      (node (ref "R22") (pin "1") (pinfunction "1_1") (pintype "passive"))
    )
    (net (code "38") (name "Net-(R23-Pad2)") (class "Default")
      (node (ref "R23") (pin "2") (pinfunction "2_2") (pintype "passive"))
      (node (ref "R24") (pin "1") (pinfunction "1_1") (pintype "passive"))
    )
    (net (code "39") (name "Net-(R25-Pad2)") (class "Default")
      (node (ref "R25") (pin "2") (pinfunction "2_2") (pintype "passive"))
      (node (ref "R26") (pin "1") (pinfunction "1_1") (pintype "passive"))
    )
    (net (code "40") (name "Net-(R27-Pad2)") (class "Default")
      (node (ref "R27") (pin "2") (pinfunction "2_2") (pintype "passive"))
      (node (ref "R28") (pin "1") (pinfunction "1_1") (pintype "passive"))
    )
    (net (code "41") (name "Net-(R29-Pad2)") (class "Default")
      (node (ref "R29") (pin "2") (pinfunction "2_2") (pintype "passive"))
      (node (ref "R30") (pin "1") (pinfunction "1_1") (pintype "passive"))
    )
    (net (code "42") (name "Net-(R31-Pad2)") (class "Default")
      (node (ref "R31") (pin "2") (pinfunction "2_2") (pintype "passive"))
      (node (ref "R32") (pin "1") (pinfunction "1_1") (pintype "passive"))
    )
    (net (code "43") (name "Net-(R33-Pad2)") (class "Default")
      (node (ref "R33") (pin "2") (pinfunction "2_2") (pintype "passive"))
      (node (ref "R34") (pin "1") (pinfunction "1_1") (pintype "passive"))
    )
    (net (code "44") (name "Net-(R35-Pad2)") (class "Default")
      (node (ref "R35") (pin "2") (pinfunction "2_2") (pintype "passive"))
      (node (ref "R36") (pin "1") (pinfunction "1_1") (pintype "passive"))
    )
    (net (code "45") (name "Net-(R37-Pad2)") (class "Default")
      (node (ref "R37") (pin "2") (pinfunction "2_2") (pintype "passive"))
      (node (ref "R38") (pin "1") (pinfunction "1_1") (pintype "passive"))
    )
    (net (code "46") (name "Net-(R39-Pad2)") (class "Default")
      (node (ref "R39") (pin "2") (pinfunction "2_2") (pintype "passive"))
      (node (ref "R40") (pin "1") (pinfunction "1_1") (pintype "passive"))
    )
    (net (code "47") (name "Net-(R41-Pad2)") (class "Default")
      (node (ref "R41") (pin "2") (pinfunction "2_2") (pintype "passive"))
      (node (ref "R42") (pin "1") (pinfunction "1_1") (pintype "passive"))
    )
    (net (code "48") (name "Net-(R43-Pad2)") (class "Default")
      (node (ref "R43") (pin "2") (pinfunction "2_2") (pintype "passive"))
      (node (ref "R44") (pin "1") (pinfunction "1_1") (pintype "passive"))
    )
    (net (code "49") (name "Net-(R45-Pad2)") (class "Default")
      (node (ref "R45") (pin "2") (pinfunction "2_2") (pintype "passive"))
      (node (ref "R46") (pin "1") (pinfunction "1_1") (pintype "passive"))
    )
    (net (code "50") (name "Net-(R47-Pad2)") (class "Default")
      (node (ref "R47") (pin "2") (pinfunction "2_2") (pintype "passive"))
      (node (ref "R48") (pin "1") (pinfunction "1_1") (pintype "passive"))
    )
    (net (code "51") (name "Net-(R49-Pad2)") (class "Default")
      (node (ref "R49") (pin "2") (pinfunction "2_2") (pintype "passive"))
      (node (ref "R50") (pin "1") (pinfunction "1_1") (pintype "passive"))
    )
    (net (code "52") (name "Net-(R51-Pad2)") (class "Default")
      (node (ref "R51") (pin "2") (pinfunction "2_2") (pintype "passive"))
      (node (ref "R52") (pin "1") (pinfunction "1_1") (pintype "passive"))
    )
    (net (code "53") (name "Net-(R53-Pad2)") (class "Default")
      (node (ref "R53") (pin "2") (pinfunction "2_2") (pintype "passive"))
      (node (ref "R54") (pin "1") (pinfunction "1_1") (pintype "passive"))
    )
    (net (code "54") (name "Net-(R55-Pad2)") (class "Default")
      (node (ref "R55") (pin "2") (pinfunction "2_2") (pintype "passive"))
      (node (ref "R56") (pin "1") (pinfunction "1_1") (pintype "passive"))
    )
    (net (code "55") (name "Net-(R57-Pad2)") (class "Default")
      (node (ref "R57") (pin "2") (pinfunction "2_2") (pintype "passive"))
      (node (ref "R58") (pin "1") (pinfunction "1_1") (pintype "passive"))
    )
    (net (code "56") (name "Net-(R59-Pad2)") (class "Default")
      (node (ref "R59") (pin "2") (pinfunction "2_2") (pintype "passive"))
      (node (ref "R60") (pin "1") (pinfunction "1_1") (pintype "passive"))
    )
    (net (code "57") (name "Net-(R61-Pad2)") (class "Default")
      (node (ref "R61") (pin "2") (pinfunction "2_2") (pintype "passive"))
      (node (ref "R62") (pin "1") (pinfunction "1_1") (pintype "passive"))
    )
    (net (code "58") (name "Net-(R63-Pad2)") (class "Default")
      (node (ref "R63") (pin "2") (pinfunction "2_2") (pintype "passive"))
      (node (ref "R64") (pin "1") (pinfunction "1_1") (pintype "passive"))
    )
  )
)
